# Sheet1.net
KiCad netlist of a schematic drawn in Altium Designer
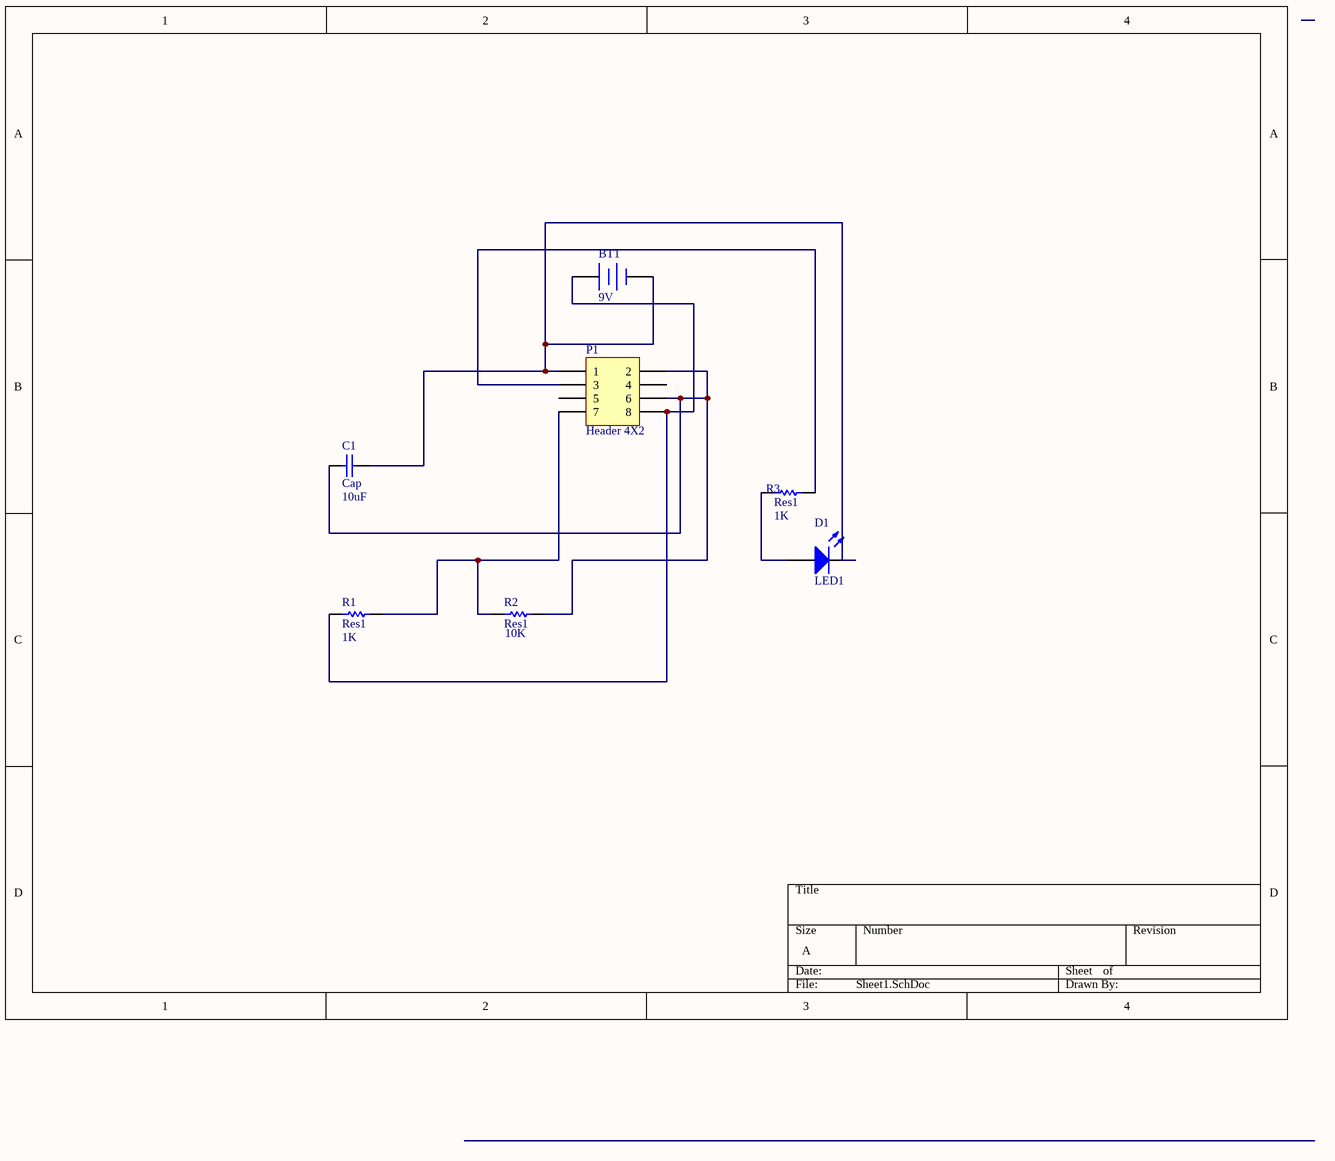
[diagram p0: Sheet1.SchDoc]

(export (version "E")
  (design (tool "Eeschema 10.0.6"))
  (components
    (comp (ref "BT1")
      (value "9V")
      (footprint "BAT-2")
      (description "Multicell Battery")
      (fields (field (name "PUBLISHER") "Altium Limited"))
      (libsource (lib "Miscellaneous Devices") (part "Battery"))
    )
    (comp (ref "C1")
      (value "Cap")
      (footprint "RAD-0.3")
      (description "Capacitor")
      (fields (field (name "ALTIUM_VALUE") "10uF") (field (name "PUBLISHER") "Altium Limited"))
      (libsource (lib "Miscellaneous Devices") (part "Cap"))
    )
    (comp (ref "D1")
      (value "LED1")
      (footprint "LED-1")
      (description "Typical RED GaAs LED")
      (fields (field (name "PUBLISHER") "Altium Limited"))
      (libsource (lib "Miscellaneous Devices") (part "LED1"))
    )
    (comp (ref "P1")
      (value "Header 4X2")
      (footprint "HDR2X4")
      (description "Header, 4-Pin, Dual row")
      (fields (field (name "PUBLISHER") "Altium Limited"))
      (libsource (lib "Miscellaneous Connectors") (part "Header 4X2"))
    )
    (comp (ref "R1")
      (value "Res1")
      (footprint "AXIAL-0.3")
      (description "Resistor")
      (fields (field (name "ALTIUM_VALUE") "1K") (field (name "PUBLISHER") "Altium Limited"))
      (libsource (lib "Miscellaneous Devices") (part "Res1"))
    )
    (comp (ref "R2")
      (value "Res1")
      (footprint "AXIAL-0.3")
      (description "Resistor")
      (fields (field (name "ALTIUM_VALUE") "10K") (field (name "PUBLISHER") "Altium Limited"))
      (libsource (lib "Miscellaneous Devices") (part "Res1"))
    )
    (comp (ref "R3")
      (value "Res1")
      (footprint "AXIAL-0.3")
      (description "Resistor")
      (fields (field (name "ALTIUM_VALUE") "1K") (field (name "PUBLISHER") "Altium Limited"))
      (libsource (lib "Miscellaneous Devices") (part "Res1"))
    )
  )
  (nets
    (net (code "1") (name "Net-(BT1-+)") (class "Default")
      (node (ref "BT1") (pin "1") (pinfunction "+_1") (pintype "passive"))
      (node (ref "P1") (pin "8") (pinfunction "8_8") (pintype "passive"))
      (node (ref "R1") (pin "1") (pinfunction "1_1") (pintype "passive"))
    )
    (net (code "2") (name "Net-(BT1--)") (class "Default")
      (node (ref "BT1") (pin "2") (pinfunction "-_2") (pintype "passive"))
      (node (ref "C1") (pin "2") (pinfunction "2_2") (pintype "passive"))
      (node (ref "D1") (pin "2") (pinfunction "K_2") (pintype "passive"))
      (node (ref "P1") (pin "1") (pinfunction "1_1") (pintype "passive"))
    )
    (net (code "3") (name "Net-(C1-Pad1)") (class "Default")
      (node (ref "C1") (pin "1") (pinfunction "1_1") (pintype "passive"))
      (node (ref "P1") (pin "2") (pinfunction "2_2") (pintype "passive"))
      (node (ref "P1") (pin "6") (pinfunction "6_6") (pintype "passive"))
      (node (ref "R2") (pin "2") (pinfunction "2_2") (pintype "passive"))
    )
    (net (code "4") (name "Net-(D1-A)") (class "Default")
      (node (ref "D1") (pin "1") (pinfunction "A_1") (pintype "passive"))
      (node (ref "R3") (pin "1") (pinfunction "1_1") (pintype "passive"))
    )
    (net (code "5") (name "Net-(P1-Pad3)") (class "Default")
      (node (ref "P1") (pin "3") (pinfunction "3_3") (pintype "passive"))
      (node (ref "R3") (pin "2") (pinfunction "2_2") (pintype "passive"))
    )
    (net (code "6") (name "Net-(P1-Pad7)") (class "Default")
      (node (ref "P1") (pin "7") (pinfunction "7_7") (pintype "passive"))
      (node (ref "R1") (pin "2") (pinfunction "2_2") (pintype "passive"))
      (node (ref "R2") (pin "1") (pinfunction "1_1") (pintype "passive"))
    )
    (net (code "7") (name "unconnected-(P1-Pad4)") (class "Default")
      (node (ref "P1") (pin "4") (pinfunction "4_4") (pintype "passive"))
    )
    (net (code "8") (name "unconnected-(P1-Pad5)") (class "Default")
      (node (ref "P1") (pin "5") (pinfunction "5_5") (pintype "passive"))
    )
  )
)
